# SCH_CheetahSpeedometer_2024-07-13.net
KiCad netlist of a schematic drawn in EasyEDA
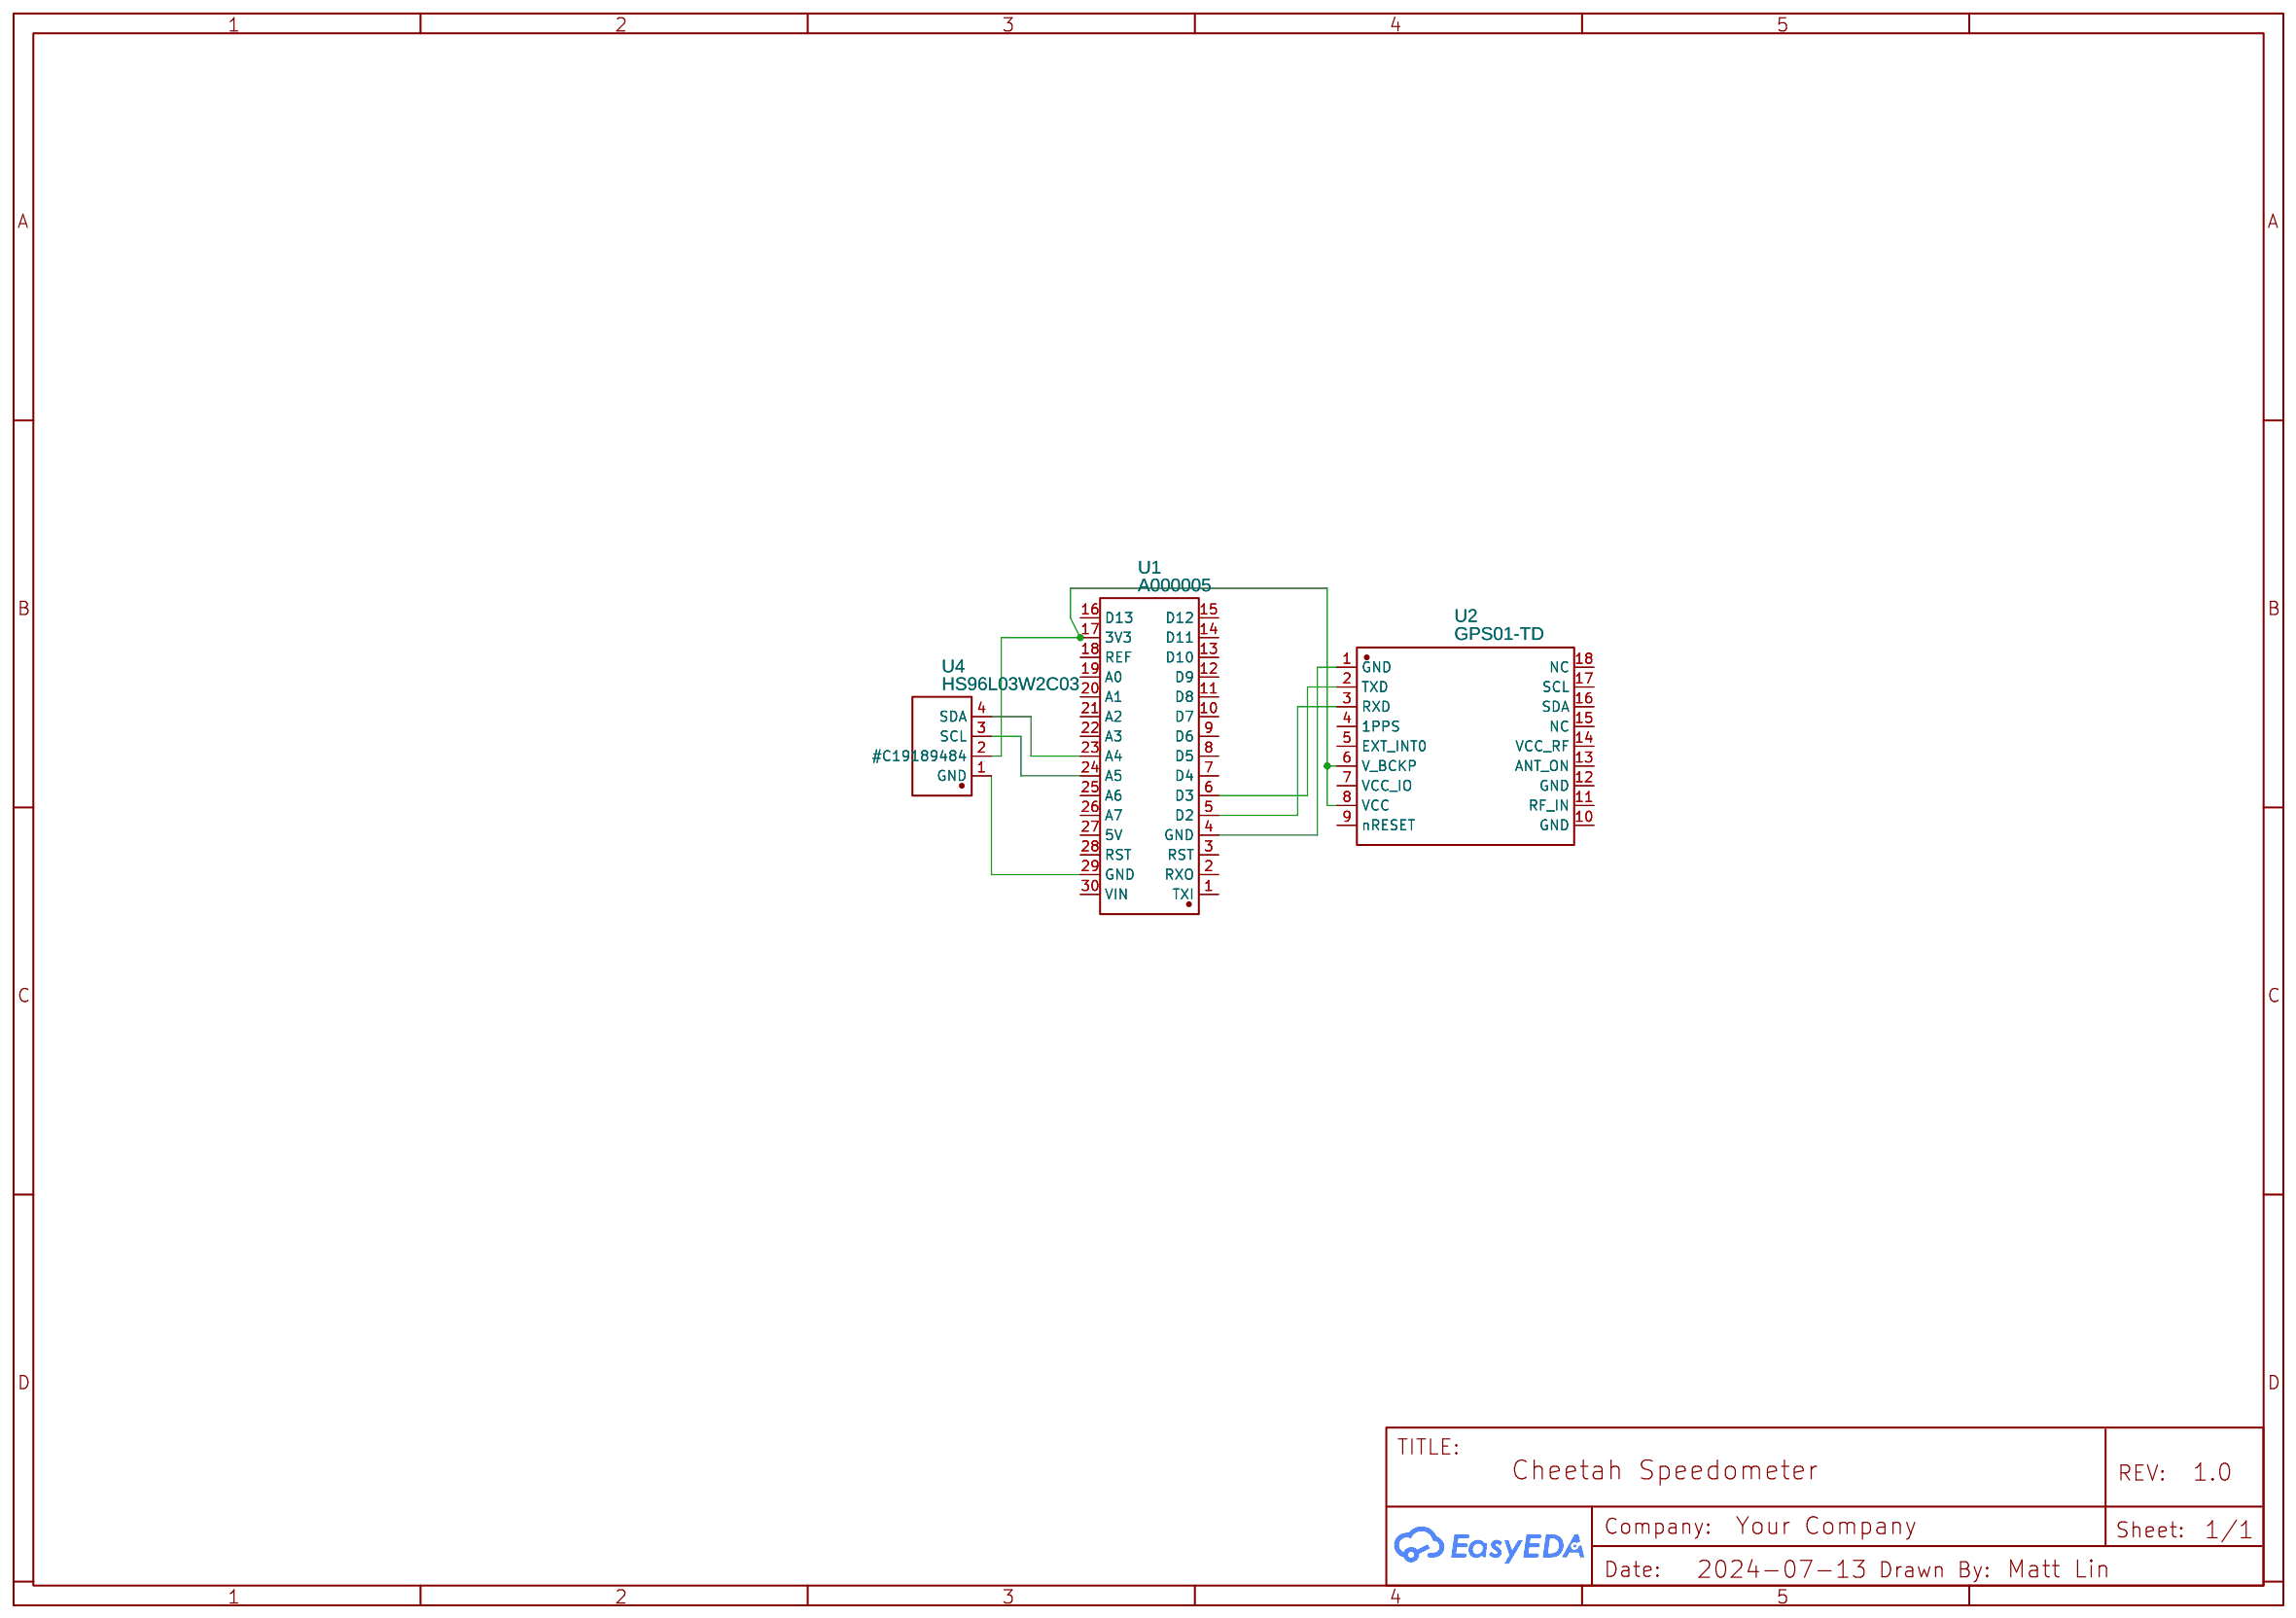
[diagram p0: schematic sheet]

(export (version "E")
  (design (tool "Eeschema 10.0.6"))
  (components
    (comp (ref "U1")
      (value "A000005")
      (fields (field (name "Manufacturer") "arduino"))
      (libsource (lib "") (part "A000005"))
    )
    (comp (ref "U2")
      (value "GPS01-TD")
      (fields (field (name "Manufacturer") "G-NiceRF(思为无线)"))
      (libsource (lib "") (part "GPS01-TD"))
    )
    (comp (ref "U4")
      (value "HS96L03W2C03")
      (fields (field (name "Manufacturer") "HS(汉昇)"))
      (libsource (lib "") (part "HS96L03W2C03"))
    )
  )
  (nets
    (net (code "1") (name "Net-(U1-3V3)") (class "Default")
      (node (ref "U1") (pin "17") (pinfunction "3V3_17") (pintype "unspecified"))
      (node (ref "U2") (pin "6") (pinfunction "V_BCKP_6") (pintype "unspecified"))
      (node (ref "U2") (pin "8") (pinfunction "VCC_8") (pintype "unspecified"))
      (node (ref "U4") (pin "2") (pinfunction "#C19189484_2") (pintype "unspecified"))
    )
    (net (code "2") (name "Net-(U1-A4)") (class "Default")
      (node (ref "U1") (pin "23") (pinfunction "A4_23") (pintype "unspecified"))
      (node (ref "U4") (pin "4") (pinfunction "SDA_4") (pintype "unspecified"))
    )
    (net (code "3") (name "Net-(U1-A5)") (class "Default")
      (node (ref "U1") (pin "24") (pinfunction "A5_24") (pintype "unspecified"))
      (node (ref "U4") (pin "3") (pinfunction "SCL_3") (pintype "unspecified"))
    )
    (net (code "4") (name "Net-(U1-D2)") (class "Default")
      (node (ref "U1") (pin "5") (pinfunction "D2_5") (pintype "unspecified"))
      (node (ref "U2") (pin "3") (pinfunction "RXD_3") (pintype "unspecified"))
    )
    (net (code "5") (name "Net-(U1-D3)") (class "Default")
      (node (ref "U1") (pin "6") (pinfunction "D3_6") (pintype "unspecified"))
      (node (ref "U2") (pin "2") (pinfunction "TXD_2") (pintype "unspecified"))
    )
    (net (code "6") (name "Net-(U1-GND-Pad4)") (class "Default")
      (node (ref "U1") (pin "4") (pinfunction "GND_4") (pintype "unspecified"))
      (node (ref "U2") (pin "1") (pinfunction "GND_1") (pintype "unspecified"))
    )
    (net (code "7") (name "Net-(U4-GND)") (class "Default")
      (node (ref "U1") (pin "29") (pinfunction "GND_29") (pintype "unspecified"))
      (node (ref "U4") (pin "1") (pinfunction "GND_1") (pintype "unspecified"))
    )
    (net (code "8") (name "unconnected-(U1-5V-Pad27)") (class "Default")
      (node (ref "U1") (pin "27") (pinfunction "5V_27") (pintype "unspecified"))
    )
    (net (code "9") (name "unconnected-(U1-A0-Pad19)") (class "Default")
      (node (ref "U1") (pin "19") (pinfunction "A0_19") (pintype "unspecified"))
    )
    (net (code "10") (name "unconnected-(U1-A1-Pad20)") (class "Default")
      (node (ref "U1") (pin "20") (pinfunction "A1_20") (pintype "unspecified"))
    )
    (net (code "11") (name "unconnected-(U1-A2-Pad21)") (class "Default")
      (node (ref "U1") (pin "21") (pinfunction "A2_21") (pintype "unspecified"))
    )
    (net (code "12") (name "unconnected-(U1-A3-Pad22)") (class "Default")
      (node (ref "U1") (pin "22") (pinfunction "A3_22") (pintype "unspecified"))
    )
    (net (code "13") (name "unconnected-(U1-A6-Pad25)") (class "Default")
      (node (ref "U1") (pin "25") (pinfunction "A6_25") (pintype "unspecified"))
    )
    (net (code "14") (name "unconnected-(U1-A7-Pad26)") (class "Default")
      (node (ref "U1") (pin "26") (pinfunction "A7_26") (pintype "unspecified"))
    )
    (net (code "15") (name "unconnected-(U1-D4-Pad7)") (class "Default")
      (node (ref "U1") (pin "7") (pinfunction "D4_7") (pintype "unspecified"))
    )
    (net (code "16") (name "unconnected-(U1-D5-Pad8)") (class "Default")
      (node (ref "U1") (pin "8") (pinfunction "D5_8") (pintype "unspecified"))
    )
    (net (code "17") (name "unconnected-(U1-D6-Pad9)") (class "Default")
      (node (ref "U1") (pin "9") (pinfunction "D6_9") (pintype "unspecified"))
    )
    (net (code "18") (name "unconnected-(U1-D7-Pad10)") (class "Default")
      (node (ref "U1") (pin "10") (pinfunction "D7_10") (pintype "unspecified"))
    )
    (net (code "19") (name "unconnected-(U1-D8-Pad11)") (class "Default")
      (node (ref "U1") (pin "11") (pinfunction "D8_11") (pintype "unspecified"))
    )
    (net (code "20") (name "unconnected-(U1-D9-Pad12)") (class "Default")
      (node (ref "U1") (pin "12") (pinfunction "D9_12") (pintype "unspecified"))
    )
    (net (code "21") (name "unconnected-(U1-D10-Pad13)") (class "Default")
      (node (ref "U1") (pin "13") (pinfunction "D10_13") (pintype "unspecified"))
    )
    (net (code "22") (name "unconnected-(U1-D11-Pad14)") (class "Default")
      (node (ref "U1") (pin "14") (pinfunction "D11_14") (pintype "unspecified"))
    )
    (net (code "23") (name "unconnected-(U1-D12-Pad15)") (class "Default")
      (node (ref "U1") (pin "15") (pinfunction "D12_15") (pintype "unspecified"))
    )
    (net (code "24") (name "unconnected-(U1-D13-Pad16)") (class "Default")
      (node (ref "U1") (pin "16") (pinfunction "D13_16") (pintype "unspecified"))
    )
    (net (code "25") (name "unconnected-(U1-REF-Pad18)") (class "Default")
      (node (ref "U1") (pin "18") (pinfunction "REF_18") (pintype "unspecified"))
    )
    (net (code "26") (name "unconnected-(U1-RST-Pad3)") (class "Default")
      (node (ref "U1") (pin "3") (pinfunction "RST_3") (pintype "unspecified"))
    )
    (net (code "27") (name "unconnected-(U1-RST-Pad28)") (class "Default")
      (node (ref "U1") (pin "28") (pinfunction "RST_28") (pintype "unspecified"))
    )
    (net (code "28") (name "unconnected-(U1-RXO-Pad2)") (class "Default")
      (node (ref "U1") (pin "2") (pinfunction "RXO_2") (pintype "unspecified"))
    )
    (net (code "29") (name "unconnected-(U1-TXI-Pad1)") (class "Default")
      (node (ref "U1") (pin "1") (pinfunction "TXI_1") (pintype "unspecified"))
    )
    (net (code "30") (name "unconnected-(U1-VIN-Pad30)") (class "Default")
      (node (ref "U1") (pin "30") (pinfunction "VIN_30") (pintype "unspecified"))
    )
    (net (code "31") (name "unconnected-(U2-1PPS-Pad4)") (class "Default")
      (node (ref "U2") (pin "4") (pinfunction "1PPS_4") (pintype "unspecified"))
    )
    (net (code "32") (name "unconnected-(U2-ANT_ON-Pad13)") (class "Default")
      (node (ref "U2") (pin "13") (pinfunction "ANT_ON_13") (pintype "unspecified"))
    )
    (net (code "33") (name "unconnected-(U2-EXT_INT0-Pad5)") (class "Default")
      (node (ref "U2") (pin "5") (pinfunction "EXT_INT0_5") (pintype "unspecified"))
    )
    (net (code "34") (name "unconnected-(U2-GND-Pad10)") (class "Default")
      (node (ref "U2") (pin "10") (pinfunction "GND_10") (pintype "unspecified"))
    )
    (net (code "35") (name "unconnected-(U2-GND-Pad12)") (class "Default")
      (node (ref "U2") (pin "12") (pinfunction "GND_12") (pintype "unspecified"))
    )
    (net (code "36") (name "unconnected-(U2-NC-Pad15)") (class "Default")
      (node (ref "U2") (pin "15") (pinfunction "NC_15") (pintype "unspecified"))
    )
    (net (code "37") (name "unconnected-(U2-NC-Pad18)") (class "Default")
      (node (ref "U2") (pin "18") (pinfunction "NC_18") (pintype "unspecified"))
    )
    (net (code "38") (name "unconnected-(U2-RF_IN-Pad11)") (class "Default")
      (node (ref "U2") (pin "11") (pinfunction "RF_IN_11") (pintype "unspecified"))
    )
    (net (code "39") (name "unconnected-(U2-SCL-Pad17)") (class "Default")
      (node (ref "U2") (pin "17") (pinfunction "SCL_17") (pintype "unspecified"))
    )
    (net (code "40") (name "unconnected-(U2-SDA-Pad16)") (class "Default")
      (node (ref "U2") (pin "16") (pinfunction "SDA_16") (pintype "unspecified"))
    )
    (net (code "41") (name "unconnected-(U2-VCC_IO-Pad7)") (class "Default")
      (node (ref "U2") (pin "7") (pinfunction "VCC_IO_7") (pintype "unspecified"))
    )
    (net (code "42") (name "unconnected-(U2-VCC_RF-Pad14)") (class "Default")
      (node (ref "U2") (pin "14") (pinfunction "VCC_RF_14") (pintype "unspecified"))
    )
    (net (code "43") (name "unconnected-(U2-nRESET-Pad9)") (class "Default")
      (node (ref "U2") (pin "9") (pinfunction "nRESET_9") (pintype "unspecified"))
    )
  )
)
